# SparkFun_TransmogriShield.net
KiCad netlist of a schematic drawn in EAGLE
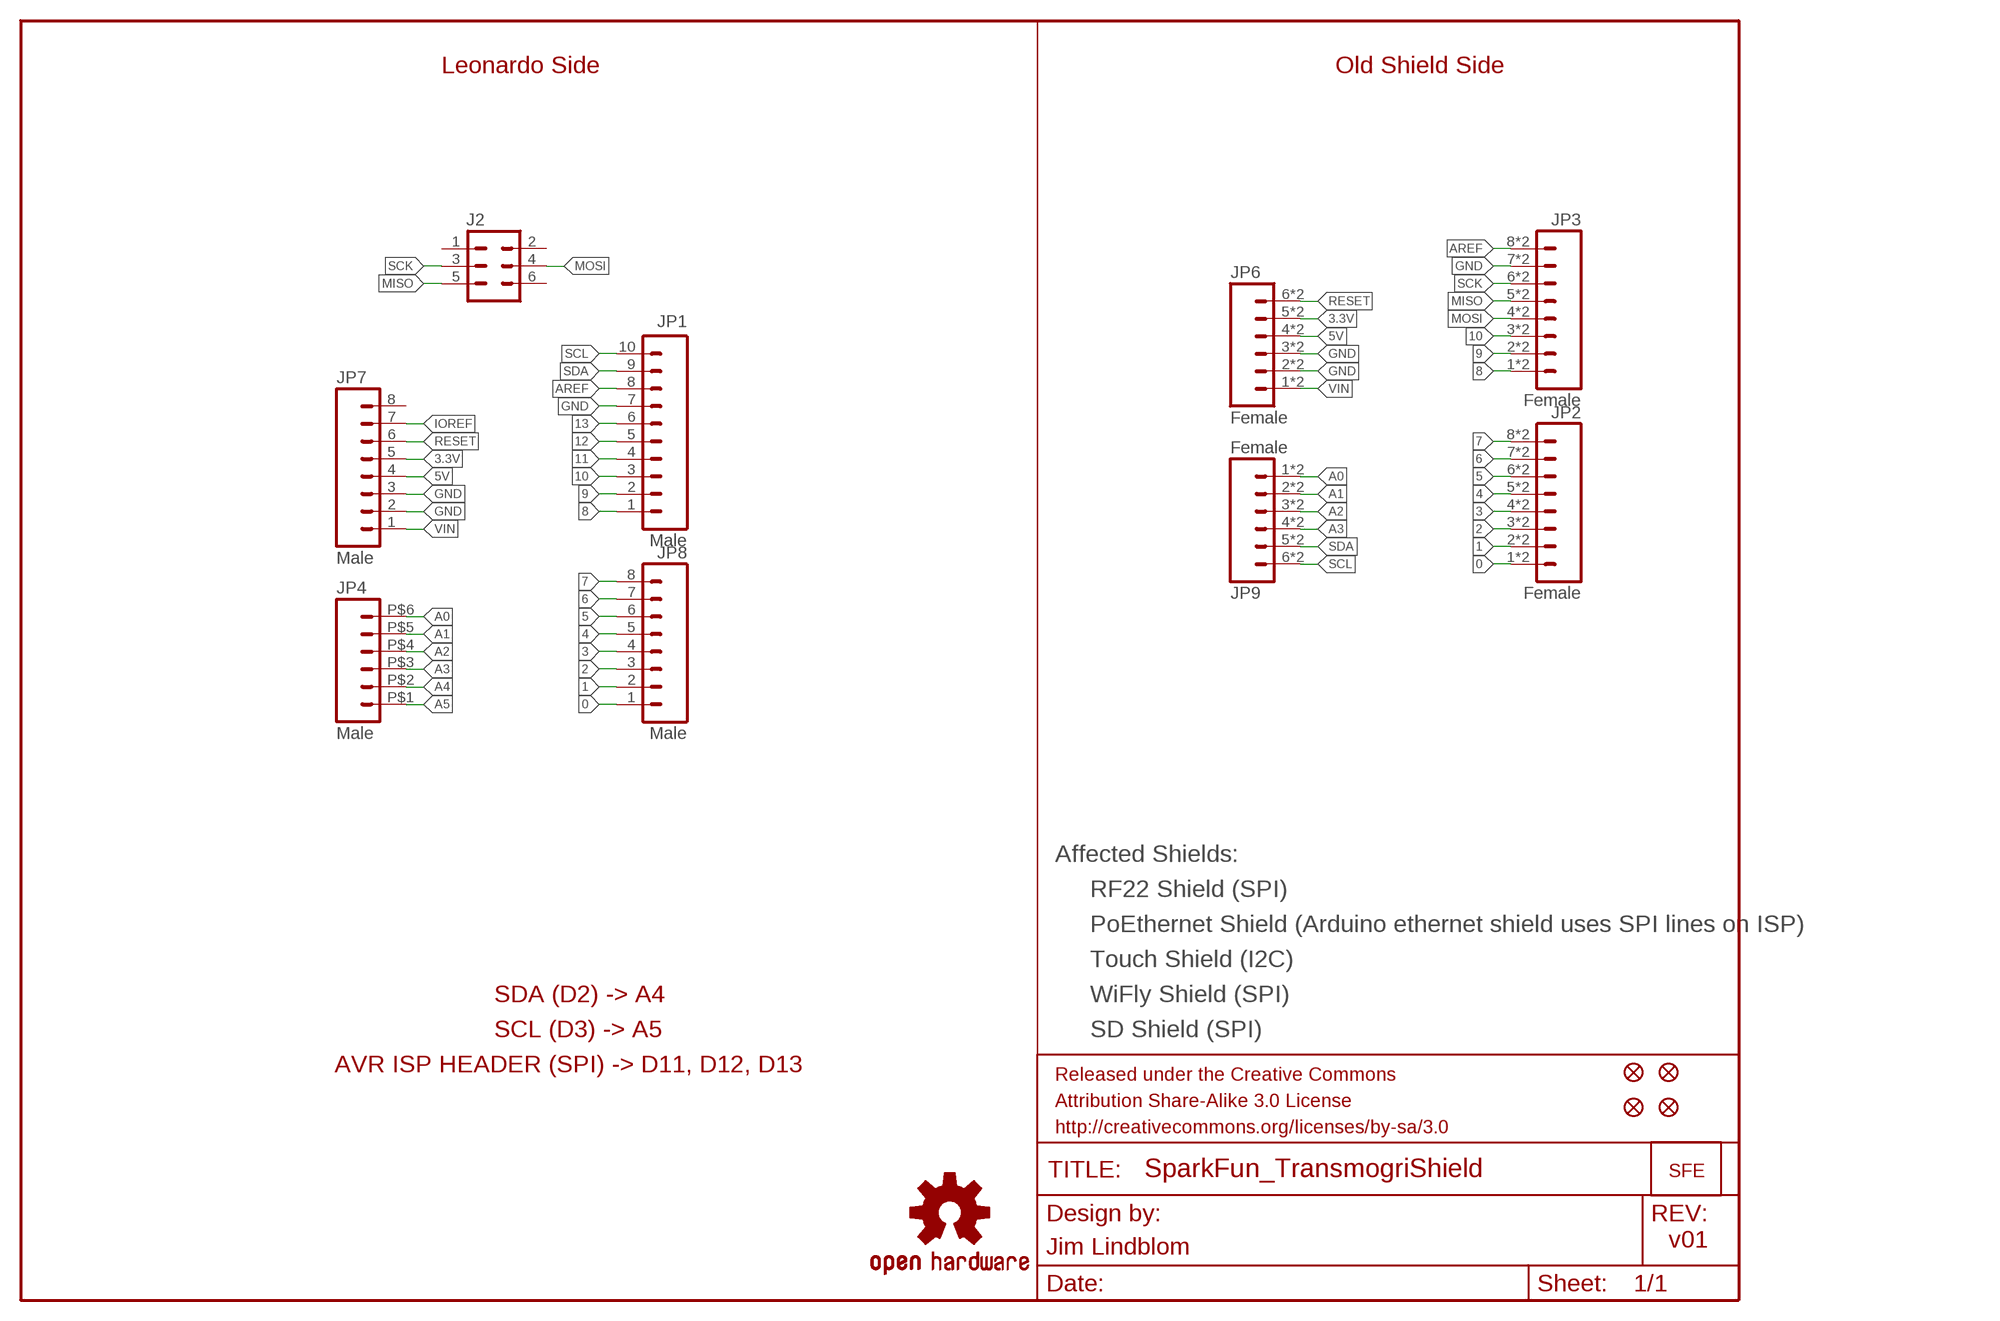
[diagram p0: schematic, sheet 1]

(export (version "E")
  (design (tool "Eeschema 10.0.6"))
  (components
    (comp (ref "J2")
      (value "Female")
      (footprint "eagle-import:2X3_SMD")
      (libsource (lib "eagle-import") (part "M03X2"))
    )
    (comp (ref "JP1")
      (value "Male")
      (footprint "eagle-import:1X10_SMD_MALE")
      (libsource (lib "eagle-import") (part "M10SMD_MALE"))
    )
    (comp (ref "JP2")
      (value "Female")
      (footprint "eagle-import:1X08_SMD_COMBINED")
      (libsource (lib "eagle-import") (part "M08SMD-COMBO"))
    )
    (comp (ref "JP3")
      (value "Female")
      (footprint "eagle-import:1X08_SMD_COMBINED")
      (libsource (lib "eagle-import") (part "M08SMD-COMBO"))
    )
    (comp (ref "JP4")
      (value "Male")
      (footprint "eagle-import:1X06_SMD_MALE")
      (libsource (lib "eagle-import") (part "M06SMD_MALE"))
    )
    (comp (ref "JP6")
      (value "Female")
      (footprint "eagle-import:1X06_SMD_STRAIGHT_COMBO")
      (libsource (lib "eagle-import") (part "M06SMD-STRAIGHT-COMBO"))
    )
    (comp (ref "JP7")
      (value "Male")
      (footprint "eagle-import:1X08_SMD_MALE")
      (libsource (lib "eagle-import") (part "M08SMD-MALE"))
    )
    (comp (ref "JP8")
      (value "Male")
      (footprint "eagle-import:1X08_SMD_MALE")
      (libsource (lib "eagle-import") (part "M08SMD-MALE"))
    )
    (comp (ref "JP9")
      (value "Female")
      (footprint "eagle-import:1X06_SMD_STRAIGHT_COMBO")
      (libsource (lib "eagle-import") (part "M06SMD-STRAIGHT-COMBO"))
    )
    (comp (ref "JP10")
      (value "LOGO-SFESK")
      (footprint "eagle-import:SFE-LOGO-FLAME")
      (libsource (lib "eagle-import") (part "LOGO-SFESK"))
    )
    (comp (ref "JP11")
      (value "FIDUCIALUFIDUCIAL")
      (footprint "eagle-import:MICRO-FIDUCIAL")
      (libsource (lib "eagle-import") (part "FIDUCIALUFIDUCIAL"))
    )
    (comp (ref "JP12")
      (value "FIDUCIALUFIDUCIAL")
      (footprint "eagle-import:MICRO-FIDUCIAL")
      (libsource (lib "eagle-import") (part "FIDUCIALUFIDUCIAL"))
    )
    (comp (ref "JP13")
      (value "FIDUCIALUFIDUCIAL")
      (footprint "eagle-import:MICRO-FIDUCIAL")
      (libsource (lib "eagle-import") (part "FIDUCIALUFIDUCIAL"))
    )
    (comp (ref "JP14")
      (value "FIDUCIALUFIDUCIAL")
      (footprint "eagle-import:MICRO-FIDUCIAL")
      (libsource (lib "eagle-import") (part "FIDUCIALUFIDUCIAL"))
    )
    (comp (ref "U$1")
      (value "OSHW-LOGOS")
      (footprint "eagle-import:OSHW-LOGO-S")
      (libsource (lib "eagle-import") (part "OSHW-LOGOS"))
    )
  )
  (nets
    (net (code "1") (name "0") (class "Default")
      (node (ref "JP2") (pin "1") (pinfunction "1_1") (pintype "passive"))
      (node (ref "JP2") (pin "1@2") (pinfunction "1_1@2") (pintype "passive"))
      (node (ref "JP8") (pin "1") (pinfunction "1_1") (pintype "passive"))
    )
    (net (code "2") (name "1") (class "Default")
      (node (ref "JP2") (pin "2") (pinfunction "2_2") (pintype "passive"))
      (node (ref "JP2") (pin "2@2") (pinfunction "2_2@2") (pintype "passive"))
      (node (ref "JP8") (pin "2") (pinfunction "2_2") (pintype "passive"))
    )
    (net (code "3") (name "2") (class "Default")
      (node (ref "JP2") (pin "3") (pinfunction "3_3") (pintype "passive"))
      (node (ref "JP2") (pin "3@2") (pinfunction "3_3@2") (pintype "passive"))
      (node (ref "JP8") (pin "3") (pinfunction "3_3") (pintype "passive"))
    )
    (net (code "4") (name "3") (class "Default")
      (node (ref "JP2") (pin "4") (pinfunction "4_4") (pintype "passive"))
      (node (ref "JP2") (pin "4@2") (pinfunction "4_4@2") (pintype "passive"))
      (node (ref "JP8") (pin "4") (pinfunction "4_4") (pintype "passive"))
    )
    (net (code "5") (name "3.3V") (class "Default")
      (node (ref "JP6") (pin "5") (pinfunction "5_5") (pintype "passive"))
      (node (ref "JP6") (pin "5-2") (pinfunction "5_5-2") (pintype "passive"))
      (node (ref "JP7") (pin "5") (pinfunction "5_5") (pintype "passive"))
    )
    (net (code "6") (name "4") (class "Default")
      (node (ref "JP2") (pin "5") (pinfunction "5_5") (pintype "passive"))
      (node (ref "JP2") (pin "5@2") (pinfunction "5_5@2") (pintype "passive"))
      (node (ref "JP8") (pin "5") (pinfunction "5_5") (pintype "passive"))
    )
    (net (code "7") (name "5") (class "Default")
      (node (ref "JP2") (pin "6") (pinfunction "6_6") (pintype "passive"))
      (node (ref "JP2") (pin "6@2") (pinfunction "6_6@2") (pintype "passive"))
      (node (ref "JP8") (pin "6") (pinfunction "6_6") (pintype "passive"))
    )
    (net (code "8") (name "5V") (class "Default")
      (node (ref "JP6") (pin "4") (pinfunction "4_4") (pintype "passive"))
      (node (ref "JP6") (pin "4-2") (pinfunction "4_4-2") (pintype "passive"))
      (node (ref "JP7") (pin "4") (pinfunction "4_4") (pintype "passive"))
    )
    (net (code "9") (name "6") (class "Default")
      (node (ref "JP2") (pin "7") (pinfunction "7_7") (pintype "passive"))
      (node (ref "JP2") (pin "7@2") (pinfunction "7_7@2") (pintype "passive"))
      (node (ref "JP8") (pin "7") (pinfunction "7_7") (pintype "passive"))
    )
    (net (code "10") (name "7") (class "Default")
      (node (ref "JP2") (pin "8") (pinfunction "8_8") (pintype "passive"))
      (node (ref "JP2") (pin "8@2") (pinfunction "8_8@2") (pintype "passive"))
      (node (ref "JP8") (pin "8") (pinfunction "8_8") (pintype "passive"))
    )
    (net (code "11") (name "8") (class "Default")
      (node (ref "JP1") (pin "1") (pinfunction "1_1") (pintype "passive"))
      (node (ref "JP3") (pin "1") (pinfunction "1_1") (pintype "passive"))
      (node (ref "JP3") (pin "1@2") (pinfunction "1_1@2") (pintype "passive"))
    )
    (net (code "12") (name "9") (class "Default")
      (node (ref "JP1") (pin "2") (pinfunction "2_2") (pintype "passive"))
      (node (ref "JP3") (pin "2") (pinfunction "2_2") (pintype "passive"))
      (node (ref "JP3") (pin "2@2") (pinfunction "2_2@2") (pintype "passive"))
    )
    (net (code "13") (name "10") (class "Default")
      (node (ref "JP1") (pin "3") (pinfunction "3_3") (pintype "passive"))
      (node (ref "JP3") (pin "3") (pinfunction "3_3") (pintype "passive"))
      (node (ref "JP3") (pin "3@2") (pinfunction "3_3@2") (pintype "passive"))
    )
    (net (code "14") (name "11") (class "Default")
      (node (ref "JP1") (pin "4") (pinfunction "4_4") (pintype "passive"))
    )
    (net (code "15") (name "12") (class "Default")
      (node (ref "JP1") (pin "5") (pinfunction "5_5") (pintype "passive"))
    )
    (net (code "16") (name "13") (class "Default")
      (node (ref "JP1") (pin "6") (pinfunction "6_6") (pintype "passive"))
    )
    (net (code "17") (name "A0") (class "Default")
      (node (ref "JP4") (pin "P$6") (pinfunction "6_P$6") (pintype "passive"))
      (node (ref "JP9") (pin "1") (pinfunction "1_1") (pintype "passive"))
      (node (ref "JP9") (pin "1-2") (pinfunction "1_1-2") (pintype "passive"))
    )
    (net (code "18") (name "A1") (class "Default")
      (node (ref "JP4") (pin "P$5") (pinfunction "5_P$5") (pintype "passive"))
      (node (ref "JP9") (pin "2") (pinfunction "2_2") (pintype "passive"))
      (node (ref "JP9") (pin "2-2") (pinfunction "2_2-2") (pintype "passive"))
    )
    (net (code "19") (name "A2") (class "Default")
      (node (ref "JP4") (pin "P$4") (pinfunction "4_P$4") (pintype "passive"))
      (node (ref "JP9") (pin "3") (pinfunction "3_3") (pintype "passive"))
      (node (ref "JP9") (pin "3-2") (pinfunction "3_3-2") (pintype "passive"))
    )
    (net (code "20") (name "A3") (class "Default")
      (node (ref "JP4") (pin "P$3") (pinfunction "3_P$3") (pintype "passive"))
      (node (ref "JP9") (pin "4") (pinfunction "4_4") (pintype "passive"))
      (node (ref "JP9") (pin "4-2") (pinfunction "4_4-2") (pintype "passive"))
    )
    (net (code "21") (name "A4") (class "Default")
      (node (ref "JP4") (pin "P$2") (pinfunction "2_P$2") (pintype "passive"))
    )
    (net (code "22") (name "A5") (class "Default")
      (node (ref "JP4") (pin "P$1") (pinfunction "1_P$1") (pintype "passive"))
    )
    (net (code "23") (name "AREF") (class "Default")
      (node (ref "JP1") (pin "8") (pinfunction "8_8") (pintype "passive"))
      (node (ref "JP3") (pin "8") (pinfunction "8_8") (pintype "passive"))
      (node (ref "JP3") (pin "8@2") (pinfunction "8_8@2") (pintype "passive"))
    )
    (net (code "24") (name "GND") (class "Default")
      (node (ref "JP1") (pin "7") (pinfunction "7_7") (pintype "passive"))
      (node (ref "JP3") (pin "7") (pinfunction "7_7") (pintype "passive"))
      (node (ref "JP3") (pin "7@2") (pinfunction "7_7@2") (pintype "passive"))
      (node (ref "JP6") (pin "2") (pinfunction "2_2") (pintype "passive"))
      (node (ref "JP6") (pin "2-2") (pinfunction "2_2-2") (pintype "passive"))
      (node (ref "JP6") (pin "3") (pinfunction "3_3") (pintype "passive"))
      (node (ref "JP6") (pin "3-2") (pinfunction "3_3-2") (pintype "passive"))
      (node (ref "JP7") (pin "2") (pinfunction "2_2") (pintype "passive"))
      (node (ref "JP7") (pin "3") (pinfunction "3_3") (pintype "passive"))
    )
    (net (code "25") (name "IOREF") (class "Default")
      (node (ref "JP7") (pin "7") (pinfunction "7_7") (pintype "passive"))
    )
    (net (code "26") (name "MISO") (class "Default")
      (node (ref "J2") (pin "5") (pinfunction "5_5") (pintype "passive"))
      (node (ref "JP3") (pin "5") (pinfunction "5_5") (pintype "passive"))
      (node (ref "JP3") (pin "5@2") (pinfunction "5_5@2") (pintype "passive"))
    )
    (net (code "27") (name "MOSI") (class "Default")
      (node (ref "J2") (pin "4") (pinfunction "4_4") (pintype "passive"))
      (node (ref "JP3") (pin "4") (pinfunction "4_4") (pintype "passive"))
      (node (ref "JP3") (pin "4@2") (pinfunction "4_4@2") (pintype "passive"))
    )
    (net (code "28") (name "RESET") (class "Default")
      (node (ref "JP6") (pin "6") (pinfunction "6_6") (pintype "passive"))
      (node (ref "JP6") (pin "6-2") (pinfunction "6_6-2") (pintype "passive"))
      (node (ref "JP7") (pin "6") (pinfunction "6_6") (pintype "passive"))
    )
    (net (code "29") (name "SCK") (class "Default")
      (node (ref "J2") (pin "3") (pinfunction "3_3") (pintype "passive"))
      (node (ref "JP3") (pin "6") (pinfunction "6_6") (pintype "passive"))
      (node (ref "JP3") (pin "6@2") (pinfunction "6_6@2") (pintype "passive"))
    )
    (net (code "30") (name "SCL") (class "Default")
      (node (ref "JP1") (pin "10") (pinfunction "10_10") (pintype "passive"))
      (node (ref "JP9") (pin "6") (pinfunction "6_6") (pintype "passive"))
      (node (ref "JP9") (pin "6-2") (pinfunction "6_6-2") (pintype "passive"))
    )
    (net (code "31") (name "SDA") (class "Default")
      (node (ref "JP1") (pin "9") (pinfunction "9_9") (pintype "passive"))
      (node (ref "JP9") (pin "5") (pinfunction "5_5") (pintype "passive"))
      (node (ref "JP9") (pin "5-2") (pinfunction "5_5-2") (pintype "passive"))
    )
    (net (code "32") (name "VIN") (class "Default")
      (node (ref "JP6") (pin "1") (pinfunction "1_1") (pintype "passive"))
      (node (ref "JP6") (pin "1-2") (pinfunction "1_1-2") (pintype "passive"))
      (node (ref "JP7") (pin "1") (pinfunction "1_1") (pintype "passive"))
    )
    (net (code "33") (name "unconnected-(J2-Pad1)") (class "Default")
      (node (ref "J2") (pin "1") (pinfunction "1_1") (pintype "passive"))
    )
    (net (code "34") (name "unconnected-(J2-Pad2)") (class "Default")
      (node (ref "J2") (pin "2") (pinfunction "2_2") (pintype "passive"))
    )
    (net (code "35") (name "unconnected-(J2-Pad6)") (class "Default")
      (node (ref "J2") (pin "6") (pinfunction "6_6") (pintype "passive"))
    )
    (net (code "36") (name "unconnected-(JP7-Pad8)") (class "Default")
      (node (ref "JP7") (pin "8") (pinfunction "8_8") (pintype "passive"))
    )
  )
)
